# SCH_TT5_14_2024-07-31.net
KiCad netlist of a schematic drawn in EasyEDA
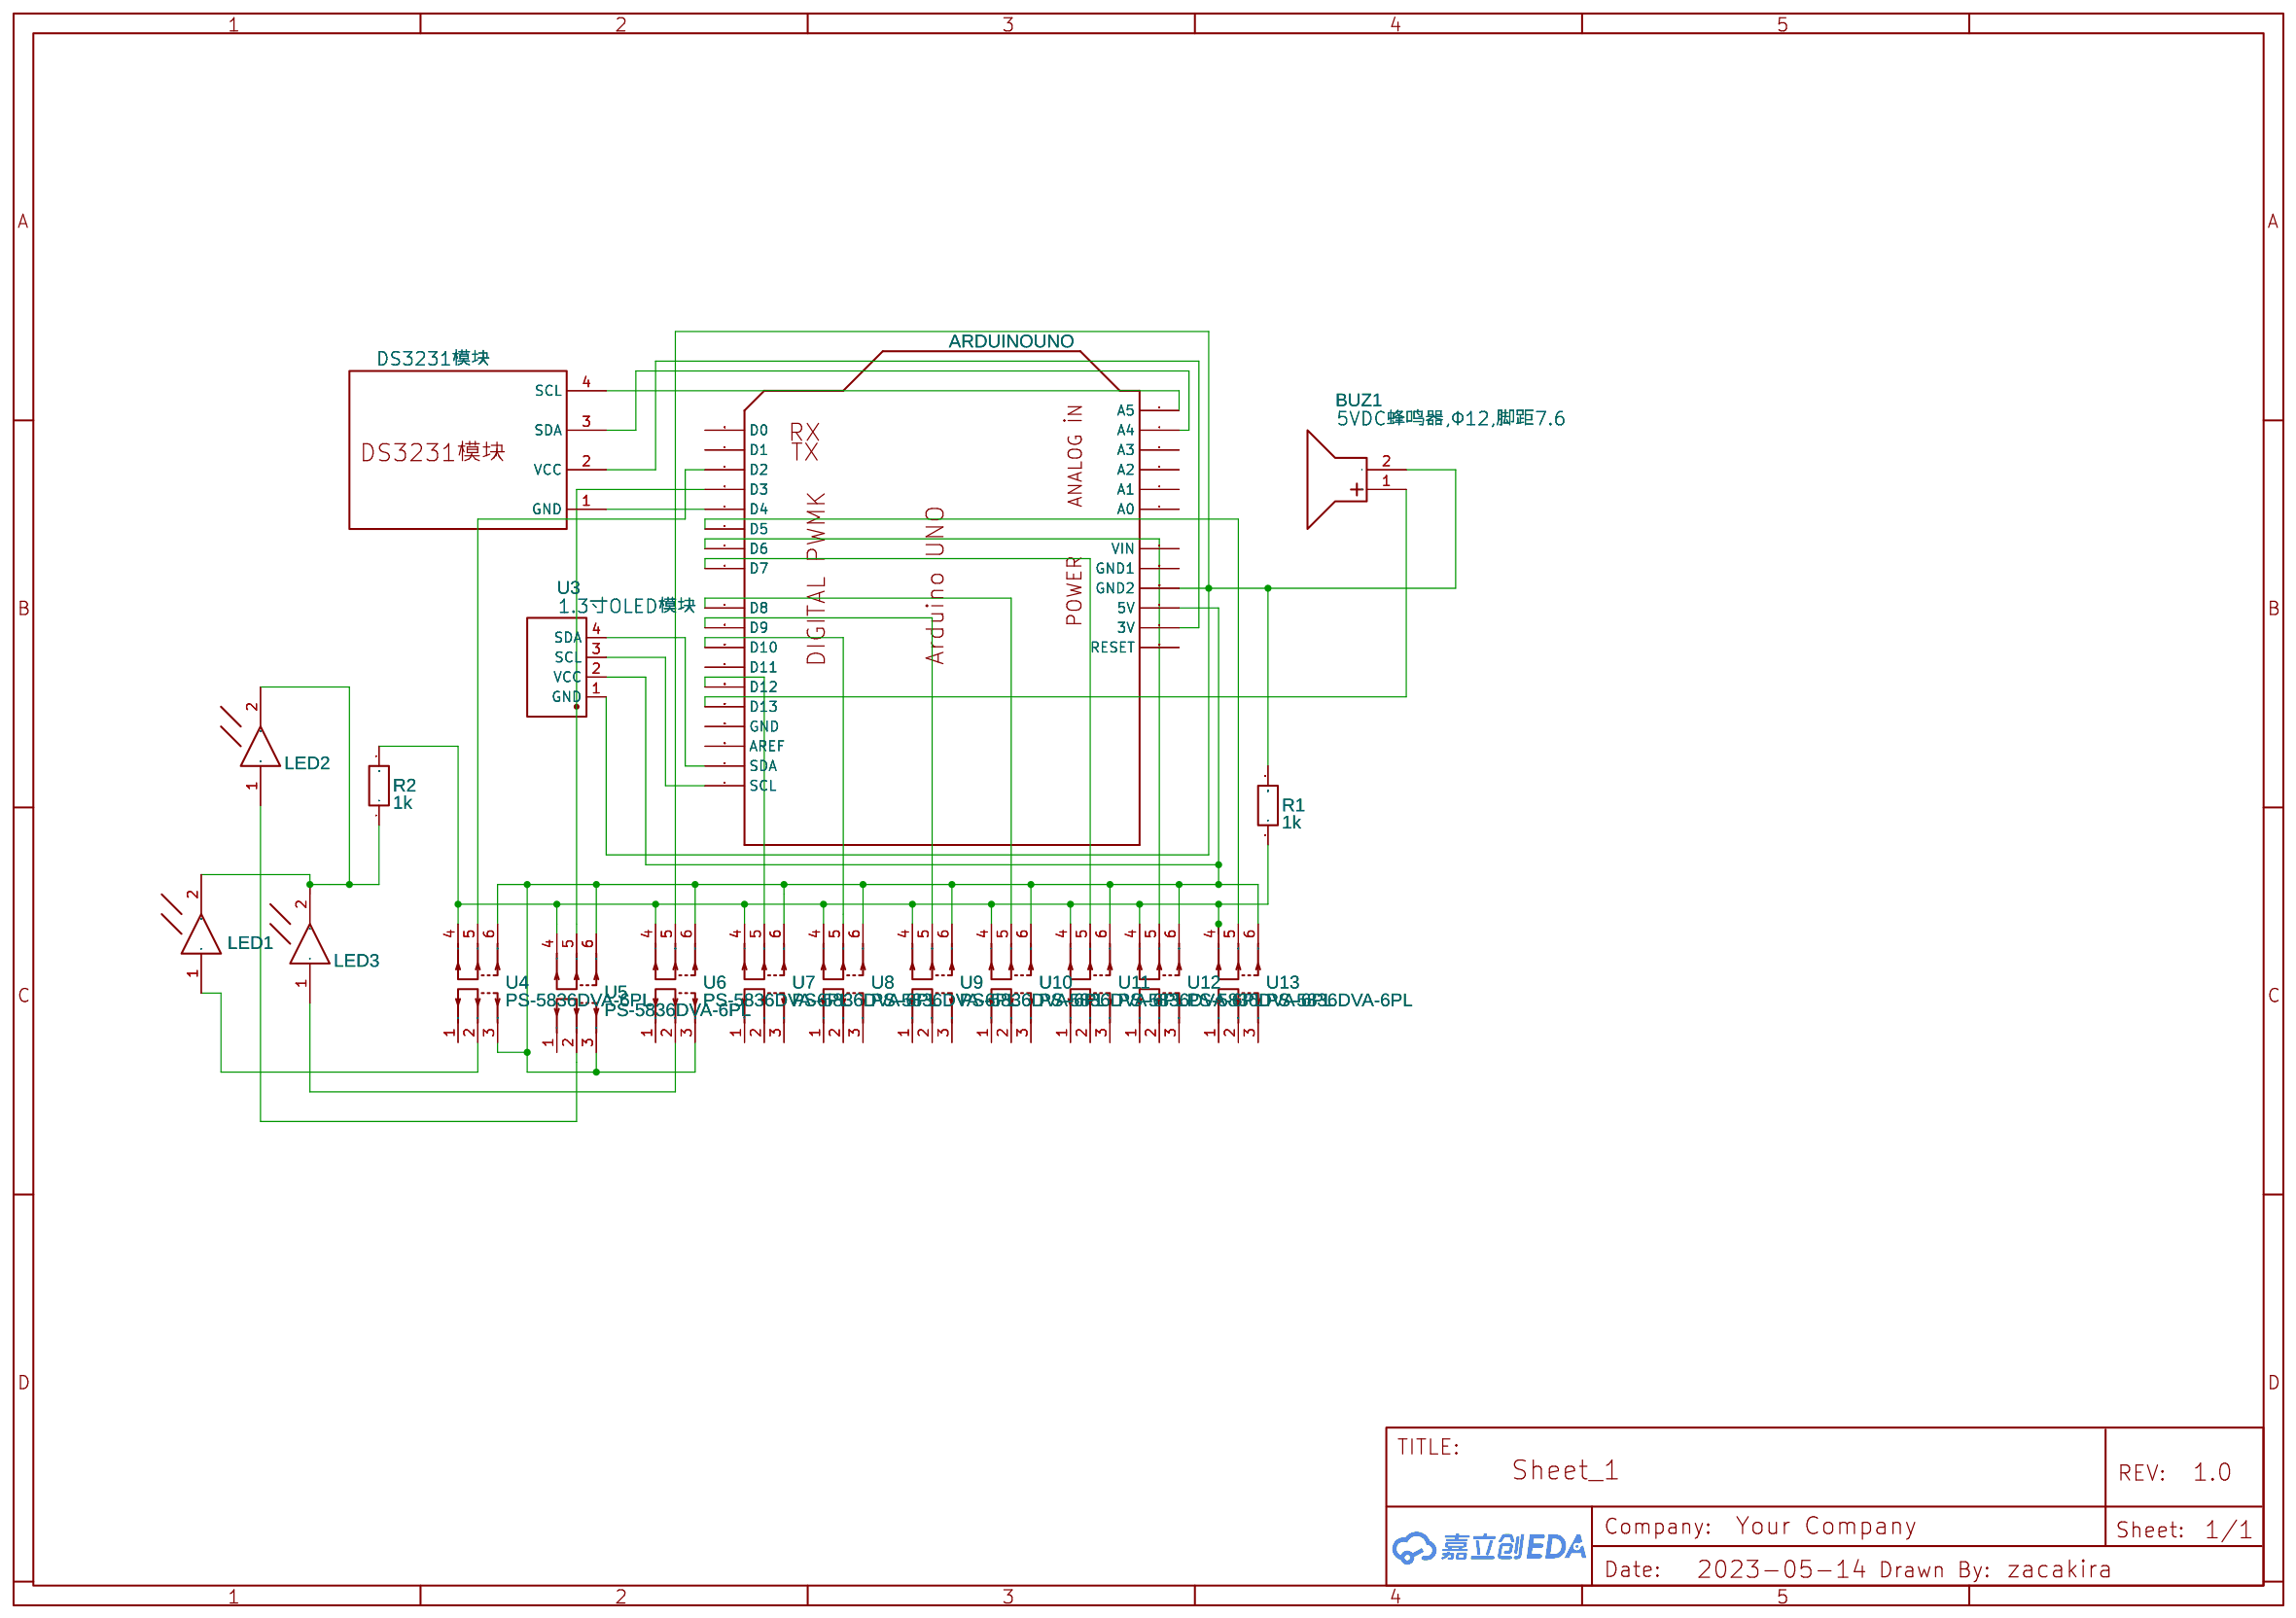
[diagram p0: schematic sheet]

(export (version "E")
  (design (tool "Eeschema 10.0.6"))
  (components
    (comp (ref "BUZ1") (value "5VDC蜂鸣器,Φ12,脚距7.6") (libsource (lib "") (part "5VDC蜂鸣器,Φ12,脚距7.6")))
    (comp (ref "R1") (value "1k") (libsource (lib "") (part "1k")))
    (comp (ref "R2") (value "1k") (libsource (lib "") (part "1k")))
    (comp (ref "U1") (value "DS3231模块") (libsource (lib "") (part "DS3231模块")))
    (comp (ref "U2") (value "ARDUINOUNO") (libsource (lib "") (part "ARDUINOUNO COPY")))
    (comp (ref "U3") (value "1.3寸OLED模块") (libsource (lib "") (part "1.3寸OLED模块")))
    (comp (ref "U4")
      (value "PS-5836DVA-6PL")
      (fields (field (name "Manufacturer") "G-Switch(品赞)"))
      (libsource (lib "") (part "PS-5836DVA-6PL"))
    )
    (comp (ref "U5")
      (value "PS-5836DVA-6PL")
      (fields (field (name "Manufacturer") "G-Switch(品赞)"))
      (libsource (lib "") (part "PS-5836DVA-6PL"))
    )
    (comp (ref "U6")
      (value "PS-5836DVA-6PL")
      (fields (field (name "Manufacturer") "G-Switch(品赞)"))
      (libsource (lib "") (part "PS-5836DVA-6PL"))
    )
    (comp (ref "U7")
      (value "PS-5836DVA-6PL")
      (fields (field (name "Manufacturer") "G-Switch(品赞)"))
      (libsource (lib "") (part "PS-5836DVA-6PL"))
    )
    (comp (ref "U8")
      (value "PS-5836DVA-6PL")
      (fields (field (name "Manufacturer") "G-Switch(品赞)"))
      (libsource (lib "") (part "PS-5836DVA-6PL"))
    )
    (comp (ref "U9")
      (value "PS-5836DVA-6PL")
      (fields (field (name "Manufacturer") "G-Switch(品赞)"))
      (libsource (lib "") (part "PS-5836DVA-6PL"))
    )
    (comp (ref "U10")
      (value "PS-5836DVA-6PL")
      (fields (field (name "Manufacturer") "G-Switch(品赞)"))
      (libsource (lib "") (part "PS-5836DVA-6PL"))
    )
    (comp (ref "U11")
      (value "PS-5836DVA-6PL")
      (fields (field (name "Manufacturer") "G-Switch(品赞)"))
      (libsource (lib "") (part "PS-5836DVA-6PL"))
    )
    (comp (ref "U12")
      (value "PS-5836DVA-6PL")
      (fields (field (name "Manufacturer") "G-Switch(品赞)"))
      (libsource (lib "") (part "PS-5836DVA-6PL"))
    )
    (comp (ref "U13")
      (value "PS-5836DVA-6PL")
      (fields (field (name "Manufacturer") "G-Switch(品赞)"))
      (libsource (lib "") (part "PS-5836DVA-6PL"))
    )
    (comp (ref "U14") (value "LED1") (libsource (lib "") (part "LED（红色 直插）")))
    (comp (ref "U15") (value "LED2") (libsource (lib "") (part "LED（红色 直插）")))
    (comp (ref "U16") (value "LED3") (libsource (lib "") (part "LED（红色 直插）")))
  )
  (nets
    (net (code "1") (name "Net-(BUZ1-+)") (class "Default")
      (node (ref "BUZ1") (pin "1") (pinfunction "+_1") (pintype "unspecified"))
      (node (ref "U2") (pin "D13") (pinfunction "D13_D13") (pintype "unspecified"))
    )
    (net (code "2") (name "Net-(BUZ1--)") (class "Default")
      (node (ref "BUZ1") (pin "2") (pinfunction "-_2") (pintype "unspecified"))
      (node (ref "R1") (pin "2") (pinfunction "0.5w_2") (pintype "unspecified"))
      (node (ref "U1") (pin "1") (pinfunction "GND_1") (pintype "unspecified"))
      (node (ref "U2") (pin "D4") (pinfunction "D4_D4") (pintype "unspecified"))
      (node (ref "U2") (pin "GND2") (pinfunction "GND2_GND2") (pintype "passive"))
      (node (ref "U3") (pin "1") (pinfunction "GND_1") (pintype "unspecified"))
      (node (ref "U6") (pin "5") (pinfunction "5_5") (pintype "unspecified"))
    )
    (net (code "3") (name "Net-(R2-0.5w)") (class "Default")
      (node (ref "R1") (pin "1") (pinfunction "1_1") (pintype "unspecified"))
      (node (ref "R2") (pin "2") (pinfunction "0.5w_2") (pintype "unspecified"))
      (node (ref "U10") (pin "4") (pinfunction "4_4") (pintype "unspecified"))
      (node (ref "U11") (pin "4") (pinfunction "4_4") (pintype "unspecified"))
      (node (ref "U12") (pin "4") (pinfunction "4_4") (pintype "unspecified"))
      (node (ref "U13") (pin "4") (pinfunction "4_4") (pintype "unspecified"))
      (node (ref "U4") (pin "4") (pinfunction "4_4") (pintype "unspecified"))
      (node (ref "U5") (pin "4") (pinfunction "4_4") (pintype "unspecified"))
      (node (ref "U6") (pin "4") (pinfunction "4_4") (pintype "unspecified"))
      (node (ref "U7") (pin "4") (pinfunction "4_4") (pintype "unspecified"))
      (node (ref "U8") (pin "4") (pinfunction "4_4") (pintype "unspecified"))
      (node (ref "U9") (pin "4") (pinfunction "4_4") (pintype "unspecified"))
    )
    (net (code "4") (name "Net-(R2-Pad1)") (class "Default")
      (node (ref "R2") (pin "1") (pinfunction "1_1") (pintype "unspecified"))
      (node (ref "U14") (pin "2") (pinfunction "2_2") (pintype "unspecified"))
      (node (ref "U15") (pin "2") (pinfunction "2_2") (pintype "unspecified"))
      (node (ref "U16") (pin "2") (pinfunction "2_2") (pintype "unspecified"))
    )
    (net (code "5") (name "Net-(U1-SCL)") (class "Default")
      (node (ref "U1") (pin "4") (pinfunction "SCL_4") (pintype "unspecified"))
      (node (ref "U2") (pin "A5") (pinfunction "A5_A5") (pintype "unspecified"))
    )
    (net (code "6") (name "Net-(U1-SDA)") (class "Default")
      (node (ref "U1") (pin "3") (pinfunction "SDA_3") (pintype "unspecified"))
      (node (ref "U2") (pin "A4") (pinfunction "A4_A4") (pintype "unspecified"))
    )
    (net (code "7") (name "Net-(U1-VCC)") (class "Default")
      (node (ref "U1") (pin "2") (pinfunction "VCC_2") (pintype "unspecified"))
      (node (ref "U2") (pin "3V") (pinfunction "3V_3V") (pintype "passive"))
    )
    (net (code "8") (name "Net-(U2-PadD2)") (class "Default")
      (node (ref "U2") (pin "D2") (pinfunction "D2_D2") (pintype "unspecified"))
      (node (ref "U4") (pin "5") (pinfunction "5_5") (pintype "unspecified"))
    )
    (net (code "9") (name "Net-(U2-PadD3)") (class "Default")
      (node (ref "U2") (pin "D3") (pinfunction "D3_D3") (pintype "unspecified"))
      (node (ref "U5") (pin "5") (pinfunction "5_5") (pintype "unspecified"))
    )
    (net (code "10") (name "Net-(U2-PadD9)") (class "Default")
      (node (ref "U2") (pin "D9") (pinfunction "D9_D9") (pintype "unspecified"))
      (node (ref "U9") (pin "5") (pinfunction "5_5") (pintype "unspecified"))
    )
    (net (code "11") (name "Net-(U2-PadD10)") (class "Default")
      (node (ref "U2") (pin "D10") (pinfunction "D10_D10") (pintype "unspecified"))
      (node (ref "U8") (pin "5") (pinfunction "5_5") (pintype "unspecified"))
    )
    (net (code "12") (name "Net-(U2-PadD12)") (class "Default")
      (node (ref "U2") (pin "D12") (pinfunction "D12_D12") (pintype "unspecified"))
      (node (ref "U7") (pin "5") (pinfunction "5_5") (pintype "unspecified"))
    )
    (net (code "13") (name "Net-(U3-SCL)") (class "Default")
      (node (ref "U2") (pin "SCL") (pinfunction "SCL_SCL") (pintype "unspecified"))
      (node (ref "U3") (pin "3") (pinfunction "SCL_3") (pintype "unspecified"))
    )
    (net (code "14") (name "Net-(U3-SDA)") (class "Default")
      (node (ref "U2") (pin "SDA") (pinfunction "SDA_SDA") (pintype "unspecified"))
      (node (ref "U3") (pin "4") (pinfunction "SDA_4") (pintype "unspecified"))
    )
    (net (code "15") (name "Net-(U3-VCC)") (class "Default")
      (node (ref "U10") (pin "6") (pinfunction "6_6") (pintype "unspecified"))
      (node (ref "U11") (pin "6") (pinfunction "6_6") (pintype "unspecified"))
      (node (ref "U12") (pin "6") (pinfunction "6_6") (pintype "unspecified"))
      (node (ref "U13") (pin "6") (pinfunction "6_6") (pintype "unspecified"))
      (node (ref "U2") (pin "5V") (pinfunction "5V_5V") (pintype "passive"))
      (node (ref "U3") (pin "2") (pinfunction "VCC_2") (pintype "unspecified"))
      (node (ref "U4") (pin "3") (pinfunction "3_3") (pintype "unspecified"))
      (node (ref "U4") (pin "6") (pinfunction "6_6") (pintype "unspecified"))
      (node (ref "U5") (pin "3") (pinfunction "3_3") (pintype "unspecified"))
      (node (ref "U5") (pin "6") (pinfunction "6_6") (pintype "unspecified"))
      (node (ref "U6") (pin "3") (pinfunction "3_3") (pintype "unspecified"))
      (node (ref "U6") (pin "6") (pinfunction "6_6") (pintype "unspecified"))
      (node (ref "U7") (pin "6") (pinfunction "6_6") (pintype "unspecified"))
      (node (ref "U8") (pin "6") (pinfunction "6_6") (pintype "unspecified"))
      (node (ref "U9") (pin "6") (pinfunction "6_6") (pintype "unspecified"))
    )
    (net (code "16") (name "Net-(U10-Pad5)") (class "Default")
      (node (ref "U10") (pin "5") (pinfunction "5_5") (pintype "unspecified"))
      (node (ref "U2") (pin "D8") (pinfunction "D8_D8") (pintype "unspecified"))
    )
    (net (code "17") (name "Net-(U11-Pad5)") (class "Default")
      (node (ref "U11") (pin "5") (pinfunction "5_5") (pintype "unspecified"))
      (node (ref "U2") (pin "D7") (pinfunction "D7_D7") (pintype "unspecified"))
    )
    (net (code "18") (name "Net-(U12-Pad5)") (class "Default")
      (node (ref "U12") (pin "5") (pinfunction "5_5") (pintype "unspecified"))
      (node (ref "U2") (pin "D6") (pinfunction "D6_D6") (pintype "unspecified"))
    )
    (net (code "19") (name "Net-(U13-Pad5)") (class "Default")
      (node (ref "U13") (pin "5") (pinfunction "5_5") (pintype "unspecified"))
      (node (ref "U2") (pin "D5") (pinfunction "D5_D5") (pintype "unspecified"))
    )
    (net (code "20") (name "Net-(U14-Pad1)") (class "Default")
      (node (ref "U14") (pin "1") (pinfunction "1_1") (pintype "unspecified"))
      (node (ref "U4") (pin "2") (pinfunction "2_2") (pintype "unspecified"))
    )
    (net (code "21") (name "Net-(U15-Pad1)") (class "Default")
      (node (ref "U15") (pin "1") (pinfunction "1_1") (pintype "unspecified"))
      (node (ref "U5") (pin "2") (pinfunction "2_2") (pintype "unspecified"))
    )
    (net (code "22") (name "Net-(U16-Pad1)") (class "Default")
      (node (ref "U16") (pin "1") (pinfunction "1_1") (pintype "unspecified"))
      (node (ref "U6") (pin "2") (pinfunction "2_2") (pintype "unspecified"))
    )
    (net (code "23") (name "unconnected-(U2-PadA0)") (class "Default")
      (node (ref "U2") (pin "A0") (pinfunction "A0_A0") (pintype "unspecified"))
    )
    (net (code "24") (name "unconnected-(U2-PadA1)") (class "Default")
      (node (ref "U2") (pin "A1") (pinfunction "A1_A1") (pintype "unspecified"))
    )
    (net (code "25") (name "unconnected-(U2-PadA2)") (class "Default")
      (node (ref "U2") (pin "A2") (pinfunction "A2_A2") (pintype "unspecified"))
    )
    (net (code "26") (name "unconnected-(U2-PadA3)") (class "Default")
      (node (ref "U2") (pin "A3") (pinfunction "A3_A3") (pintype "unspecified"))
    )
    (net (code "27") (name "unconnected-(U2-PadAREF)") (class "Default")
      (node (ref "U2") (pin "AREF") (pinfunction "AREF_AREF") (pintype "unspecified"))
    )
    (net (code "28") (name "unconnected-(U2-PadD0)") (class "Default")
      (node (ref "U2") (pin "D0") (pinfunction "D0_D0") (pintype "unspecified"))
    )
    (net (code "29") (name "unconnected-(U2-PadD1)") (class "Default")
      (node (ref "U2") (pin "D1") (pinfunction "D1_D1") (pintype "unspecified"))
    )
    (net (code "30") (name "unconnected-(U2-PadD11)") (class "Default")
      (node (ref "U2") (pin "D11") (pinfunction "D11_D11") (pintype "unspecified"))
    )
    (net (code "31") (name "unconnected-(U2-PadGND)") (class "Default")
      (node (ref "U2") (pin "GND") (pinfunction "GND_GND") (pintype "passive"))
    )
    (net (code "32") (name "unconnected-(U2-PadGND1)") (class "Default")
      (node (ref "U2") (pin "GND1") (pinfunction "GND1_GND1") (pintype "passive"))
    )
    (net (code "33") (name "unconnected-(U2-PadRESET)") (class "Default")
      (node (ref "U2") (pin "RESET") (pinfunction "RESET_RESET") (pintype "unspecified"))
    )
    (net (code "34") (name "unconnected-(U2-PadVIN)") (class "Default")
      (node (ref "U2") (pin "VIN") (pinfunction "VIN_VIN") (pintype "passive"))
    )
    (net (code "35") (name "unconnected-(U4-Pad1)") (class "Default")
      (node (ref "U4") (pin "1") (pinfunction "1_1") (pintype "unspecified"))
    )
    (net (code "36") (name "unconnected-(U5-Pad1)") (class "Default")
      (node (ref "U5") (pin "1") (pinfunction "1_1") (pintype "unspecified"))
    )
    (net (code "37") (name "unconnected-(U6-Pad1)") (class "Default")
      (node (ref "U6") (pin "1") (pinfunction "1_1") (pintype "unspecified"))
    )
    (net (code "38") (name "unconnected-(U7-Pad1)") (class "Default")
      (node (ref "U7") (pin "1") (pinfunction "1_1") (pintype "unspecified"))
    )
    (net (code "39") (name "unconnected-(U7-Pad2)") (class "Default")
      (node (ref "U7") (pin "2") (pinfunction "2_2") (pintype "unspecified"))
    )
    (net (code "40") (name "unconnected-(U7-Pad3)") (class "Default")
      (node (ref "U7") (pin "3") (pinfunction "3_3") (pintype "unspecified"))
    )
    (net (code "41") (name "unconnected-(U8-Pad1)") (class "Default")
      (node (ref "U8") (pin "1") (pinfunction "1_1") (pintype "unspecified"))
    )
    (net (code "42") (name "unconnected-(U8-Pad2)") (class "Default")
      (node (ref "U8") (pin "2") (pinfunction "2_2") (pintype "unspecified"))
    )
    (net (code "43") (name "unconnected-(U8-Pad3)") (class "Default")
      (node (ref "U8") (pin "3") (pinfunction "3_3") (pintype "unspecified"))
    )
    (net (code "44") (name "unconnected-(U9-Pad1)") (class "Default")
      (node (ref "U9") (pin "1") (pinfunction "1_1") (pintype "unspecified"))
    )
    (net (code "45") (name "unconnected-(U9-Pad2)") (class "Default")
      (node (ref "U9") (pin "2") (pinfunction "2_2") (pintype "unspecified"))
    )
    (net (code "46") (name "unconnected-(U9-Pad3)") (class "Default")
      (node (ref "U9") (pin "3") (pinfunction "3_3") (pintype "unspecified"))
    )
    (net (code "47") (name "unconnected-(U10-Pad1)") (class "Default")
      (node (ref "U10") (pin "1") (pinfunction "1_1") (pintype "unspecified"))
    )
    (net (code "48") (name "unconnected-(U10-Pad2)") (class "Default")
      (node (ref "U10") (pin "2") (pinfunction "2_2") (pintype "unspecified"))
    )
    (net (code "49") (name "unconnected-(U10-Pad3)") (class "Default")
      (node (ref "U10") (pin "3") (pinfunction "3_3") (pintype "unspecified"))
    )
    (net (code "50") (name "unconnected-(U11-Pad1)") (class "Default")
      (node (ref "U11") (pin "1") (pinfunction "1_1") (pintype "unspecified"))
    )
    (net (code "51") (name "unconnected-(U11-Pad2)") (class "Default")
      (node (ref "U11") (pin "2") (pinfunction "2_2") (pintype "unspecified"))
    )
    (net (code "52") (name "unconnected-(U11-Pad3)") (class "Default")
      (node (ref "U11") (pin "3") (pinfunction "3_3") (pintype "unspecified"))
    )
    (net (code "53") (name "unconnected-(U12-Pad1)") (class "Default")
      (node (ref "U12") (pin "1") (pinfunction "1_1") (pintype "unspecified"))
    )
    (net (code "54") (name "unconnected-(U12-Pad2)") (class "Default")
      (node (ref "U12") (pin "2") (pinfunction "2_2") (pintype "unspecified"))
    )
    (net (code "55") (name "unconnected-(U12-Pad3)") (class "Default")
      (node (ref "U12") (pin "3") (pinfunction "3_3") (pintype "unspecified"))
    )
    (net (code "56") (name "unconnected-(U13-Pad1)") (class "Default")
      (node (ref "U13") (pin "1") (pinfunction "1_1") (pintype "unspecified"))
    )
    (net (code "57") (name "unconnected-(U13-Pad2)") (class "Default")
      (node (ref "U13") (pin "2") (pinfunction "2_2") (pintype "unspecified"))
    )
    (net (code "58") (name "unconnected-(U13-Pad3)") (class "Default")
      (node (ref "U13") (pin "3") (pinfunction "3_3") (pintype "unspecified"))
    )
  )
)
